# SimPL_IMU_v1_0_DEC19.net
KiCad netlist of a schematic drawn in Altium Designer
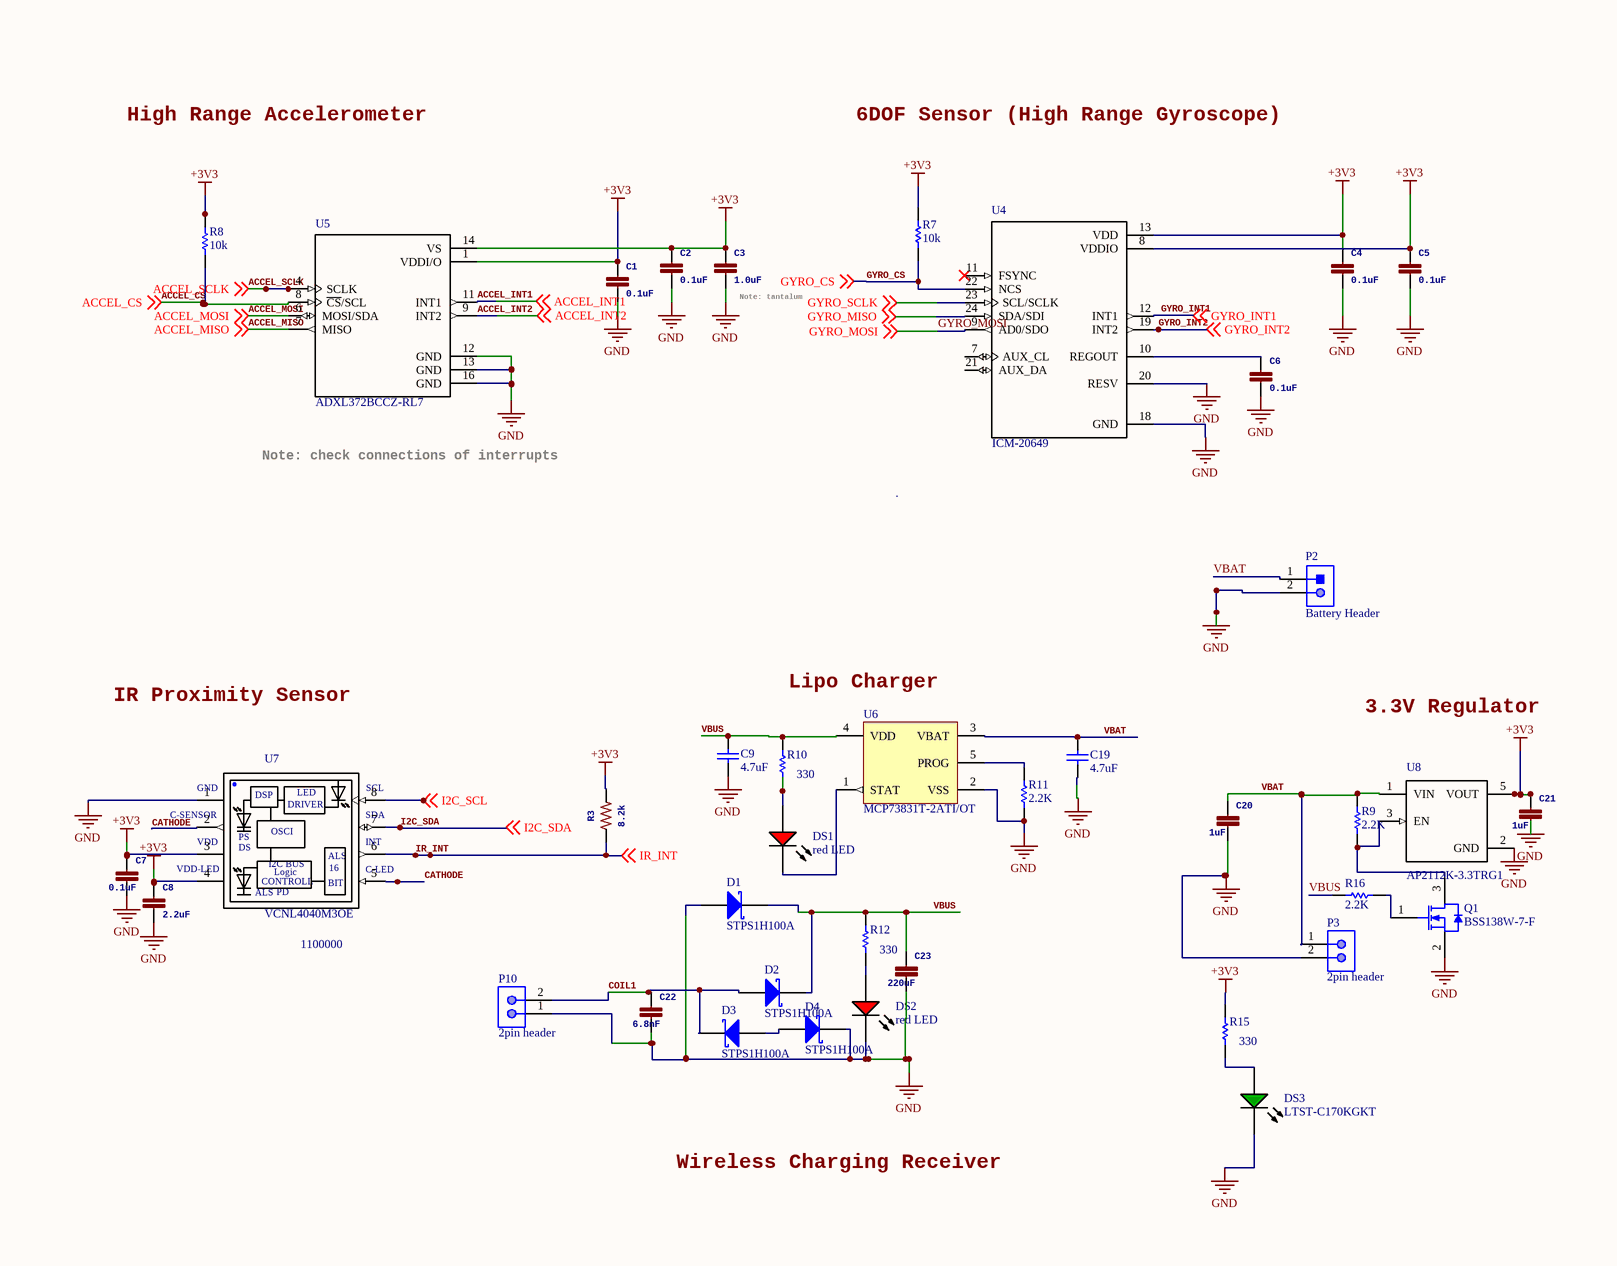
[diagram p0: SimPL_IMU_v1_0_DEC19.SchDoc]

(export (version "E")
  (design (tool "Eeschema 10.0.6"))
  (components
    (comp (ref "C1")
      (value "0.1uF")
      (footprint "0402")
      (libsource (lib "SparkFun-Capacitors") (part "0.1UF-0402-16V-10%"))
    )
    (comp (ref "C2")
      (value "0.1uF")
      (footprint "0402")
      (libsource (lib "SparkFun-Capacitors") (part "0.1UF-0402-16V-10%"))
    )
    (comp (ref "C3")
      (value "1.0uF")
      (footprint "0402")
      (libsource (lib "SparkFun-Capacitors") (part "1.0UF-0402-16V-10%"))
    )
    (comp (ref "C4")
      (value "0.1uF")
      (footprint "0402")
      (libsource (lib "SparkFun-Capacitors") (part "0.1UF-0402-16V-10%"))
    )
    (comp (ref "C5")
      (value "0.1uF")
      (footprint "0402")
      (libsource (lib "SparkFun-Capacitors") (part "0.1UF-0402-16V-10%"))
    )
    (comp (ref "C6")
      (value "0.1uF")
      (footprint "0402")
      (libsource (lib "SparkFun-Capacitors") (part "0.1UF-0402-16V-10%"))
    )
    (comp (ref "C7")
      (value "0.1uF")
      (footprint "0402")
      (libsource (lib "SparkFun-Capacitors") (part "0.1UF-0402-16V-10%"))
    )
    (comp (ref "C8")
      (value "2.2uF")
      (footprint "0402")
      (libsource (lib "SparkFun-Capacitors") (part "0.1UF-0402-16V-10%"))
    )
    (comp (ref "C9")
      (value "4.7uF")
      (footprint "CAPC1005X65X10ML15")
      (description "Chip Capacitor, 4.7 uF, +/- 20%, 10 V, -55 to 85 degC, 0402 (1005 Metric), RoHS, Tape and Reel")
      (fields
        (field (name "TOLERANCE") "±20%")
        (field (name "PCN PART NUMBER") "MLCCPartNumberChange30/Nov/2012")
      )
      (libsource (lib "Altium Content Vault") (part "CAP-NP-2"))
    )
    (comp (ref "C19")
      (value "4.7uF")
      (footprint "CAPC1005X65X10ML15")
      (description "Chip Capacitor, 4.7 uF, +/- 20%, 10 V, -55 to 85 degC, 0402 (1005 Metric), RoHS, Tape and Reel")
      (fields
        (field (name "TOLERANCE") "±20%")
        (field (name "PCN PART NUMBER") "MLCCPartNumberChange30/Nov/2012")
      )
      (libsource (lib "Altium Content Vault") (part "CAP-NP-2"))
    )
    (comp (ref "C20")
      (value "1uF")
      (footprint "0402")
      (libsource (lib "SparkFun-Capacitors") (part "0.1UF-0402-16V-10%"))
    )
    (comp (ref "C21")
      (value "1uF")
      (footprint "0402")
      (libsource (lib "SparkFun-Capacitors") (part "0.1UF-0402-16V-10%"))
    )
    (comp (ref "C22")
      (value "6.8nF")
      (footprint "0402")
      (libsource (lib "SparkFun-Capacitors") (part "0.1UF-0402-16V-10%"))
    )
    (comp (ref "C23")
      (value "220uF")
      (footprint "0402")
      (libsource (lib "SparkFun-Capacitors") (part "0.1UF-0402-16V-10%"))
    )
    (comp (ref "D1")
      (value "STPS1H100A")
      (footprint "STM-SMA-2_V")
      (description "High Voltage Power Schottky Rectifier, 1 A, 100 V, 2-Pin SMD (SMA), RoHS, Tape and Reel")
      (fields (field (name "MANUFACTURER") "STMicroelectronics"))
      (libsource (lib "Altium Content Vault") (part "DSKY-AK-2"))
    )
    (comp (ref "D2")
      (value "STPS1H100A")
      (footprint "STM-SMA-2_V")
      (description "High Voltage Power Schottky Rectifier, 1 A, 100 V, 2-Pin SMD (SMA), RoHS, Tape and Reel")
      (fields (field (name "MANUFACTURER") "STMicroelectronics"))
      (libsource (lib "Altium Content Vault") (part "DSKY-AK-2"))
    )
    (comp (ref "D3")
      (value "STPS1H100A")
      (footprint "STM-SMA-2_V")
      (description "High Voltage Power Schottky Rectifier, 1 A, 100 V, 2-Pin SMD (SMA), RoHS, Tape and Reel")
      (fields (field (name "MANUFACTURER") "STMicroelectronics"))
      (libsource (lib "Altium Content Vault") (part "DSKY-AK-2"))
    )
    (comp (ref "D4")
      (value "STPS1H100A")
      (footprint "STM-SMA-2_V")
      (description "High Voltage Power Schottky Rectifier, 1 A, 100 V, 2-Pin SMD (SMA), RoHS, Tape and Reel")
      (fields (field (name "MANUFACTURER") "STMicroelectronics"))
      (libsource (lib "Altium Content Vault") (part "DSKY-AK-2"))
    )
    (comp (ref "DS1")
      (value "red LED")
      (footprint "VISH-TLMS1000_V")
      (description "Low Current LED, 40 mW, 1.8 V, -40 to 100 degC, 2-Pin SMD (0603), RoHS, Tape and Reel")
      (fields (field (name "MANUFACTURER") "Vishay"))
      (libsource (lib "Altium Content Vault") (part "LED-RED-AK-2"))
    )
    (comp (ref "DS2")
      (value "red LED")
      (footprint "VISH-TLMS1000_V")
      (description "Low Current LED, 40 mW, 1.8 V, -40 to 100 degC, 2-Pin SMD (0603), RoHS, Tape and Reel")
      (fields (field (name "MANUFACTURER") "Vishay"))
      (libsource (lib "Altium Content Vault") (part "LED-RED-AK-2"))
    )
    (comp (ref "DS3")
      (value "LTST-C170KGKT")
      (footprint "LTST-LTST-C170KGKT-2_V")
      (description "Ultra Bright AlInGaP Chip LED, 75 mW, -55 to 85 degC, 2-Pin SMD (0805), RoHS, Tape and Reel")
      (fields (field (name "MANUFACTURER") "Lite-On"))
      (libsource (lib "Altium Content Vault") (part "LED-GREEN-KA-2"))
    )
    (comp (ref "P2")
      (value "Battery Header")
      (footprint "JST-S2B-PH-K-S_V")
      (fields (field (name "TOLERANCE") "20%"))
      (libsource (lib "") (part "CN-1P-M-R2_1"))
    )
    (comp (ref "P3")
      (value "2pin header")
      (footprint "AMPH-68000-102HLF_V")
      (description "Male Header, Pitch 2.54 mm, 1 x 2 Position, Height 8.38 mm, Tail Length 2.41 mm, RoHS, Bulk")
      (fields (field (name "MANUFACTURER") "FCI"))
      (libsource (lib "") (part "CN-1P-M-R2_2"))
    )
    (comp (ref "P10")
      (value "2pin header")
      (footprint "AMPH-68000-102HLF_V")
      (description "Male Header, Pitch 2.54 mm, 1 x 2 Position, Height 8.38 mm, Tail Length 2.41 mm, RoHS, Bulk")
      (fields (field (name "MANUFACTURER") "FCI"))
      (libsource (lib "Altium Content Vault") (part "CN-1P-M-R2"))
    )
    (comp (ref "Q1")
      (value "BSS138W-7-F")
      (footprint "DIOD-SOT323-3_V")
      (fields (field (name "MANUFACTURER") "DiodesIncorporated"))
      (libsource (lib "Altium Content Vault") (part "NEMOS-GSD-3"))
    )
    (comp (ref "R3")
      (value "8.2k")
      (footprint "0603")
      (libsource (lib "SparkFun-Resistors") (part "8.2KOHM-0603-1/10W-5%"))
    )
    (comp (ref "R7")
      (value "10k")
      (footprint "RESC1005X40X25NL05T05")
      (description "Chip Resistor, 10 KOhm, +/- 1%, 100 mW, -55 to 155 degC, 0402 (1005 Metric), RoHS, Tape and Reel")
      (fields (field (name "MANUFACTURER") "Basic Passives") (field (name "TOLERANCE") "1%"))
      (libsource (lib "Altium Content Vault") (part "RES-2"))
    )
    (comp (ref "R8")
      (value "10k")
      (footprint "RESC1005X40X25NL05T05")
      (description "Chip Resistor, 10 KOhm, +/- 1%, 100 mW, -55 to 155 degC, 0402 (1005 Metric), RoHS, Tape and Reel")
      (fields (field (name "MANUFACTURER") "Basic Passives") (field (name "TOLERANCE") "1%"))
      (libsource (lib "Altium Content Vault") (part "RES-2"))
    )
    (comp (ref "R9")
      (value "2.2K")
      (footprint "RESC1005X40X25ML10T10")
      (fields (field (name "PART NUMBER") "MC00625W040212K2") (field (name "MANUFACTURER") "Multicomp"))
      (libsource (lib "Altium Content Vault") (part "RES"))
    )
    (comp (ref "R10")
      (value "330")
      (footprint "RESC2013X50X30NL20T20")
      (fields (field (name "MANUFACTURER") "Vishay Dale") (field (name "PART NUMBER") "CRCW0805330RFKEA"))
      (libsource (lib "Altium Content Vault") (part "RES"))
    )
    (comp (ref "R11")
      (value "2.2K")
      (footprint "RESC1005X40X25ML10T10")
      (fields (field (name "PART NUMBER") "MC00625W040212K2") (field (name "MANUFACTURER") "Multicomp"))
      (libsource (lib "Altium Content Vault") (part "RES"))
    )
    (comp (ref "R12")
      (value "330")
      (footprint "RESC2013X50X30NL20T20")
      (fields (field (name "MANUFACTURER") "Vishay Dale") (field (name "PART NUMBER") "CRCW0805330RFKEA"))
      (libsource (lib "Altium Content Vault") (part "RES"))
    )
    (comp (ref "R15")
      (value "330")
      (footprint "RESC2013X50X30NL20T20")
      (fields (field (name "MANUFACTURER") "Vishay Dale") (field (name "PART NUMBER") "CRCW0805330RFKEA"))
      (libsource (lib "Altium Content Vault") (part "RES"))
    )
    (comp (ref "R16")
      (value "2.2K")
      (footprint "RESC1005X40X25ML10T10")
      (fields (field (name "PART NUMBER") "MC00625W040212K2") (field (name "MANUFACTURER") "Multicomp"))
      (libsource (lib "Altium Content Vault") (part "RES"))
    )
    (comp (ref "U4")
      (value "ICM-20649")
      (footprint "*QFN40P300X300X95-24N")
      (description "Wide-Range 6-Axis MEMS MotionTracking Device for Sports and High Impact Applications")
      (fields (field (name "MF") "TDK InvenSense"))
      (libsource (lib "ICM-20649") (part "ICM-20649"))
    )
    (comp (ref "U5")
      (value "ADXL372BCCZ-RL7")
      (footprint "*PQFN50P322X300X114-16N")
      (description "Accelerometer Triple Â±200g 2.5V 16-Pin LGA T/R")
      (fields (field (name "MF") "Analog Devices"))
      (libsource (lib "ADXL372BCCZ-RL7") (part "ADXL372BCCZ-RL7"))
    )
    (comp (ref "U6")
      (value "MCP73831T-2ATI/OT")
      (footprint "SOT-23-OT5_M")
      (libsource (lib "Altium Content Vault") (part "PM-BM-MCP73831-SOT5"))
    )
    (comp (ref "U7")
      (value "VCNL4040M3OE")
      (footprint "*VISHAY_VCNL4040_4X2X1.1")
      (description "VCNL4040 Series 3.6 V 200 mm 16 Bit I2C SMT Proximity and Ambient Light Sensor")
      (fields (field (name "MF") "Vishay"))
      (libsource (lib "VCNL4040M3OE") (part "VCNL4040M3OE"))
    )
    (comp (ref "U8")
      (value "AP2112K-3.3TRG1")
      (footprint "*SOT95P285X140-5N")
      (description "AP2112 Series 0.6 A 3.3 V Fixed Output SMT LDO Linear Regulator - SOT23-5")
      (fields (field (name "MF") "Diodes Inc."))
      (libsource (lib "AP2112K-3.3TRG1") (part "AP2112K-3.3TRG1"))
    )
  )
  (nets
    (net (code "1") (name "+3V3") (class "Default")
      (node (ref "C1") (pin "1") (pinfunction "1_1") (pintype "passive"))
      (node (ref "C2") (pin "1") (pinfunction "1_1") (pintype "passive"))
      (node (ref "C21") (pin "1") (pinfunction "1_1") (pintype "passive"))
      (node (ref "C3") (pin "1") (pinfunction "1_1") (pintype "passive"))
      (node (ref "C4") (pin "1") (pinfunction "1_1") (pintype "passive"))
      (node (ref "C5") (pin "1") (pinfunction "1_1") (pintype "passive"))
      (node (ref "C7") (pin "1") (pinfunction "1_1") (pintype "passive"))
      (node (ref "C8") (pin "1") (pinfunction "1_1") (pintype "passive"))
      (node (ref "R15") (pin "2") (pinfunction "2_2") (pintype "passive"))
      (node (ref "R3") (pin "2") (pinfunction "2_2") (pintype "passive"))
      (node (ref "R7") (pin "2") (pinfunction "2_2") (pintype "passive"))
      (node (ref "R8") (pin "2") (pinfunction "2_2") (pintype "passive"))
      (node (ref "U4") (pin "13") (pinfunction "VDD_13") (pintype "power_in"))
      (node (ref "U4") (pin "8") (pinfunction "VDDIO_8") (pintype "power_in"))
      (node (ref "U5") (pin "1") (pinfunction "VDDI/O_1") (pintype "power_in"))
      (node (ref "U5") (pin "14") (pinfunction "VS_14") (pintype "power_in"))
      (node (ref "U7") (pin "3") (pinfunction "VDD_3") (pintype "power_in"))
      (node (ref "U7") (pin "4") (pinfunction "VDD-LED_4") (pintype "power_in"))
      (node (ref "U8") (pin "5") (pinfunction "VOUT_5") (pintype "power_in"))
    )
    (net (code "2") (name "/CATHODE") (class "Default")
      (node (ref "U7") (pin "2") (pinfunction "C-SENSOR_2") (pintype "output"))
      (node (ref "U7") (pin "5") (pinfunction "C-LED_5") (pintype "input"))
    )
    (net (code "3") (name "/COIL1") (class "Default")
      (node (ref "C22") (pin "1") (pinfunction "1_1") (pintype "passive"))
      (node (ref "D2") (pin "1") (pinfunction "A_1") (pintype "passive"))
      (node (ref "D3") (pin "2") (pinfunction "K_2") (pintype "passive"))
      (node (ref "P10") (pin "2") (pinfunction "2_2") (pintype "passive"))
    )
    (net (code "4") (name "/VBAT") (class "Default")
      (node (ref "C19") (pin "2") (pinfunction "2_2") (pintype "passive"))
      (node (ref "C20") (pin "1") (pinfunction "1_1") (pintype "passive"))
      (node (ref "P2") (pin "1") (pinfunction "1_1") (pintype "passive"))
      (node (ref "P3") (pin "1") (pinfunction "1_1") (pintype "passive"))
      (node (ref "R9") (pin "2") (pinfunction "2_2") (pintype "passive"))
      (node (ref "U6") (pin "3") (pinfunction "VBAT_3") (pintype "power_in"))
      (node (ref "U8") (pin "1") (pinfunction "VIN_1") (pintype "power_in"))
    )
    (net (code "5") (name "/VBUS") (class "Default")
      (node (ref "C23") (pin "1") (pinfunction "1_1") (pintype "passive"))
      (node (ref "C9") (pin "2") (pinfunction "2_2") (pintype "passive"))
      (node (ref "D1") (pin "2") (pinfunction "K_2") (pintype "passive"))
      (node (ref "D2") (pin "2") (pinfunction "K_2") (pintype "passive"))
      (node (ref "R10") (pin "2") (pinfunction "2_2") (pintype "passive"))
      (node (ref "R12") (pin "2") (pinfunction "2_2") (pintype "passive"))
      (node (ref "R16") (pin "2") (pinfunction "2_2") (pintype "passive"))
      (node (ref "U6") (pin "4") (pinfunction "VDD_4") (pintype "power_in"))
    )
    (net (code "6") (name "ACCEL_CS") (class "Default")
      (node (ref "R8") (pin "1") (pinfunction "1_1") (pintype "passive"))
      (node (ref "U5") (pin "8") (pinfunction "~{CS}/SCL_8") (pintype "input"))
    )
    (net (code "7") (name "ACCEL_INT1") (class "Default")
      (node (ref "U5") (pin "11") (pinfunction "INT1_11") (pintype "output"))
    )
    (net (code "8") (name "ACCEL_INT2") (class "Default")
      (node (ref "U5") (pin "9") (pinfunction "INT2_9") (pintype "output"))
    )
    (net (code "9") (name "ACCEL_MISO") (class "Default")
      (node (ref "U5") (pin "7") (pinfunction "MISO_7") (pintype "output"))
    )
    (net (code "10") (name "ACCEL_MOSI") (class "Default")
      (node (ref "U5") (pin "6") (pinfunction "MOSI/SDA_6") (pintype "bidirectional"))
    )
    (net (code "11") (name "ACCEL_SCLK") (class "Default")
      (node (ref "U5") (pin "4") (pinfunction "SCLK_4") (pintype "input"))
    )
    (net (code "12") (name "GND") (class "Default")
      (node (ref "C1") (pin "2") (pinfunction "2_2") (pintype "passive"))
      (node (ref "C19") (pin "1") (pinfunction "1_1") (pintype "passive"))
      (node (ref "C2") (pin "2") (pinfunction "2_2") (pintype "passive"))
      (node (ref "C20") (pin "2") (pinfunction "2_2") (pintype "passive"))
      (node (ref "C21") (pin "2") (pinfunction "2_2") (pintype "passive"))
      (node (ref "C22") (pin "2") (pinfunction "2_2") (pintype "passive"))
      (node (ref "C23") (pin "2") (pinfunction "2_2") (pintype "passive"))
      (node (ref "C3") (pin "2") (pinfunction "2_2") (pintype "passive"))
      (node (ref "C4") (pin "2") (pinfunction "2_2") (pintype "passive"))
      (node (ref "C5") (pin "2") (pinfunction "2_2") (pintype "passive"))
      (node (ref "C6") (pin "2") (pinfunction "2_2") (pintype "passive"))
      (node (ref "C7") (pin "2") (pinfunction "2_2") (pintype "passive"))
      (node (ref "C8") (pin "2") (pinfunction "2_2") (pintype "passive"))
      (node (ref "C9") (pin "1") (pinfunction "1_1") (pintype "passive"))
      (node (ref "D1") (pin "1") (pinfunction "A_1") (pintype "passive"))
      (node (ref "D4") (pin "2") (pinfunction "K_2") (pintype "passive"))
      (node (ref "DS2") (pin "2") (pinfunction "K_2") (pintype "passive"))
      (node (ref "DS3") (pin "1") (pinfunction "K_1") (pintype "passive"))
      (node (ref "P10") (pin "1") (pinfunction "1_1") (pintype "passive"))
      (node (ref "P2") (pin "2") (pinfunction "2_2") (pintype "passive"))
      (node (ref "P3") (pin "2") (pinfunction "2_2") (pintype "passive"))
      (node (ref "Q1") (pin "2") (pinfunction "S_2") (pintype "passive"))
      (node (ref "R11") (pin "1") (pinfunction "1_1") (pintype "passive"))
      (node (ref "U4") (pin "18") (pinfunction "GND_18") (pintype "power_in"))
      (node (ref "U4") (pin "20") (pinfunction "RESV_20") (pintype "passive"))
      (node (ref "U5") (pin "12") (pinfunction "GND_12") (pintype "power_in"))
      (node (ref "U5") (pin "13") (pinfunction "GND_13") (pintype "power_in"))
      (node (ref "U5") (pin "16") (pinfunction "GND_16") (pintype "power_in"))
      (node (ref "U6") (pin "2") (pinfunction "VSS_2") (pintype "power_in"))
      (node (ref "U7") (pin "1") (pinfunction "GND_1") (pintype "power_in"))
      (node (ref "U8") (pin "2") (pinfunction "GND_2") (pintype "power_in"))
    )
    (net (code "13") (name "GYRO_CS") (class "Default")
      (node (ref "R7") (pin "1") (pinfunction "1_1") (pintype "passive"))
      (node (ref "U4") (pin "22") (pinfunction "NCS_22") (pintype "input"))
    )
    (net (code "14") (name "GYRO_INT1") (class "Default")
      (node (ref "U4") (pin "12") (pinfunction "INT1_12") (pintype "output"))
    )
    (net (code "15") (name "GYRO_INT2") (class "Default")
      (node (ref "U4") (pin "19") (pinfunction "INT2_19") (pintype "output"))
    )
    (net (code "16") (name "GYRO_MISO") (class "Default")
      (node (ref "U4") (pin "24") (pinfunction "SDA/SDI_24") (pintype "input"))
    )
    (net (code "17") (name "GYRO_MOSI") (class "Default")
      (node (ref "U4") (pin "9") (pinfunction "AD0/SDO_9") (pintype "output"))
    )
    (net (code "18") (name "GYRO_SCLK") (class "Default")
      (node (ref "U4") (pin "23") (pinfunction "SCL/SCLK_23") (pintype "input"))
    )
    (net (code "19") (name "I2C_SCL") (class "Default")
      (node (ref "U7") (pin "8") (pinfunction "SCL_8") (pintype "input"))
    )
    (net (code "20") (name "I2C_SDA") (class "Default")
      (node (ref "U7") (pin "7") (pinfunction "SDA_7") (pintype "bidirectional"))
    )
    (net (code "21") (name "IR_INT") (class "Default")
      (node (ref "R3") (pin "1") (pinfunction "1_1") (pintype "passive"))
      (node (ref "U7") (pin "6") (pinfunction "INT_6") (pintype "output"))
    )
    (net (code "22") (name "Net-(D3-A)") (class "Default")
      (node (ref "D3") (pin "1") (pinfunction "A_1") (pintype "passive"))
      (node (ref "D4") (pin "1") (pinfunction "A_1") (pintype "passive"))
    )
    (net (code "23") (name "Net-(DS1-A)") (class "Default")
      (node (ref "DS1") (pin "1") (pinfunction "A_1") (pintype "passive"))
      (node (ref "R10") (pin "1") (pinfunction "1_1") (pintype "passive"))
    )
    (net (code "24") (name "Net-(DS1-K)") (class "Default")
      (node (ref "DS1") (pin "2") (pinfunction "K_2") (pintype "passive"))
      (node (ref "U6") (pin "1") (pinfunction "STAT_1") (pintype "output"))
    )
    (net (code "25") (name "Net-(DS2-A)") (class "Default")
      (node (ref "DS2") (pin "1") (pinfunction "A_1") (pintype "passive"))
      (node (ref "R12") (pin "1") (pinfunction "1_1") (pintype "passive"))
    )
    (net (code "26") (name "Net-(DS3-A)") (class "Default")
      (node (ref "DS3") (pin "2") (pinfunction "A_2") (pintype "passive"))
      (node (ref "R15") (pin "1") (pinfunction "1_1") (pintype "passive"))
    )
    (net (code "27") (name "Net-(Q1-D)") (class "Default")
      (node (ref "Q1") (pin "3") (pinfunction "D_3") (pintype "passive"))
      (node (ref "R9") (pin "1") (pinfunction "1_1") (pintype "passive"))
      (node (ref "U8") (pin "3") (pinfunction "EN_3") (pintype "input"))
    )
    (net (code "28") (name "Net-(Q1-G)") (class "Default")
      (node (ref "Q1") (pin "1") (pinfunction "G_1") (pintype "passive"))
      (node (ref "R16") (pin "1") (pinfunction "1_1") (pintype "passive"))
    )
    (net (code "29") (name "Net-(U4-REGOUT)") (class "Default")
      (node (ref "C6") (pin "1") (pinfunction "1_1") (pintype "passive"))
      (node (ref "U4") (pin "10") (pinfunction "REGOUT_10") (pintype "passive"))
    )
    (net (code "30") (name "Net-(U6-PROG)") (class "Default")
      (node (ref "R11") (pin "2") (pinfunction "2_2") (pintype "passive"))
      (node (ref "U6") (pin "5") (pinfunction "PROG_5") (pintype "passive"))
    )
    (net (code "31") (name "unconnected-(U4-AUX_CL-Pad7)") (class "Default")
      (node (ref "U4") (pin "7") (pinfunction "AUX_CL_7") (pintype "bidirectional"))
    )
    (net (code "32") (name "unconnected-(U4-AUX_DA-Pad21)") (class "Default")
      (node (ref "U4") (pin "21") (pinfunction "AUX_DA_21") (pintype "bidirectional"))
    )
    (net (code "33") (name "unconnected-(U4-FSYNC-Pad11)") (class "Default")
      (node (ref "U4") (pin "11") (pinfunction "FSYNC_11") (pintype "input+no_connect"))
    )
  )
)
